# schematic.net
KiCad netlist of a schematic drawn in EasyEDA
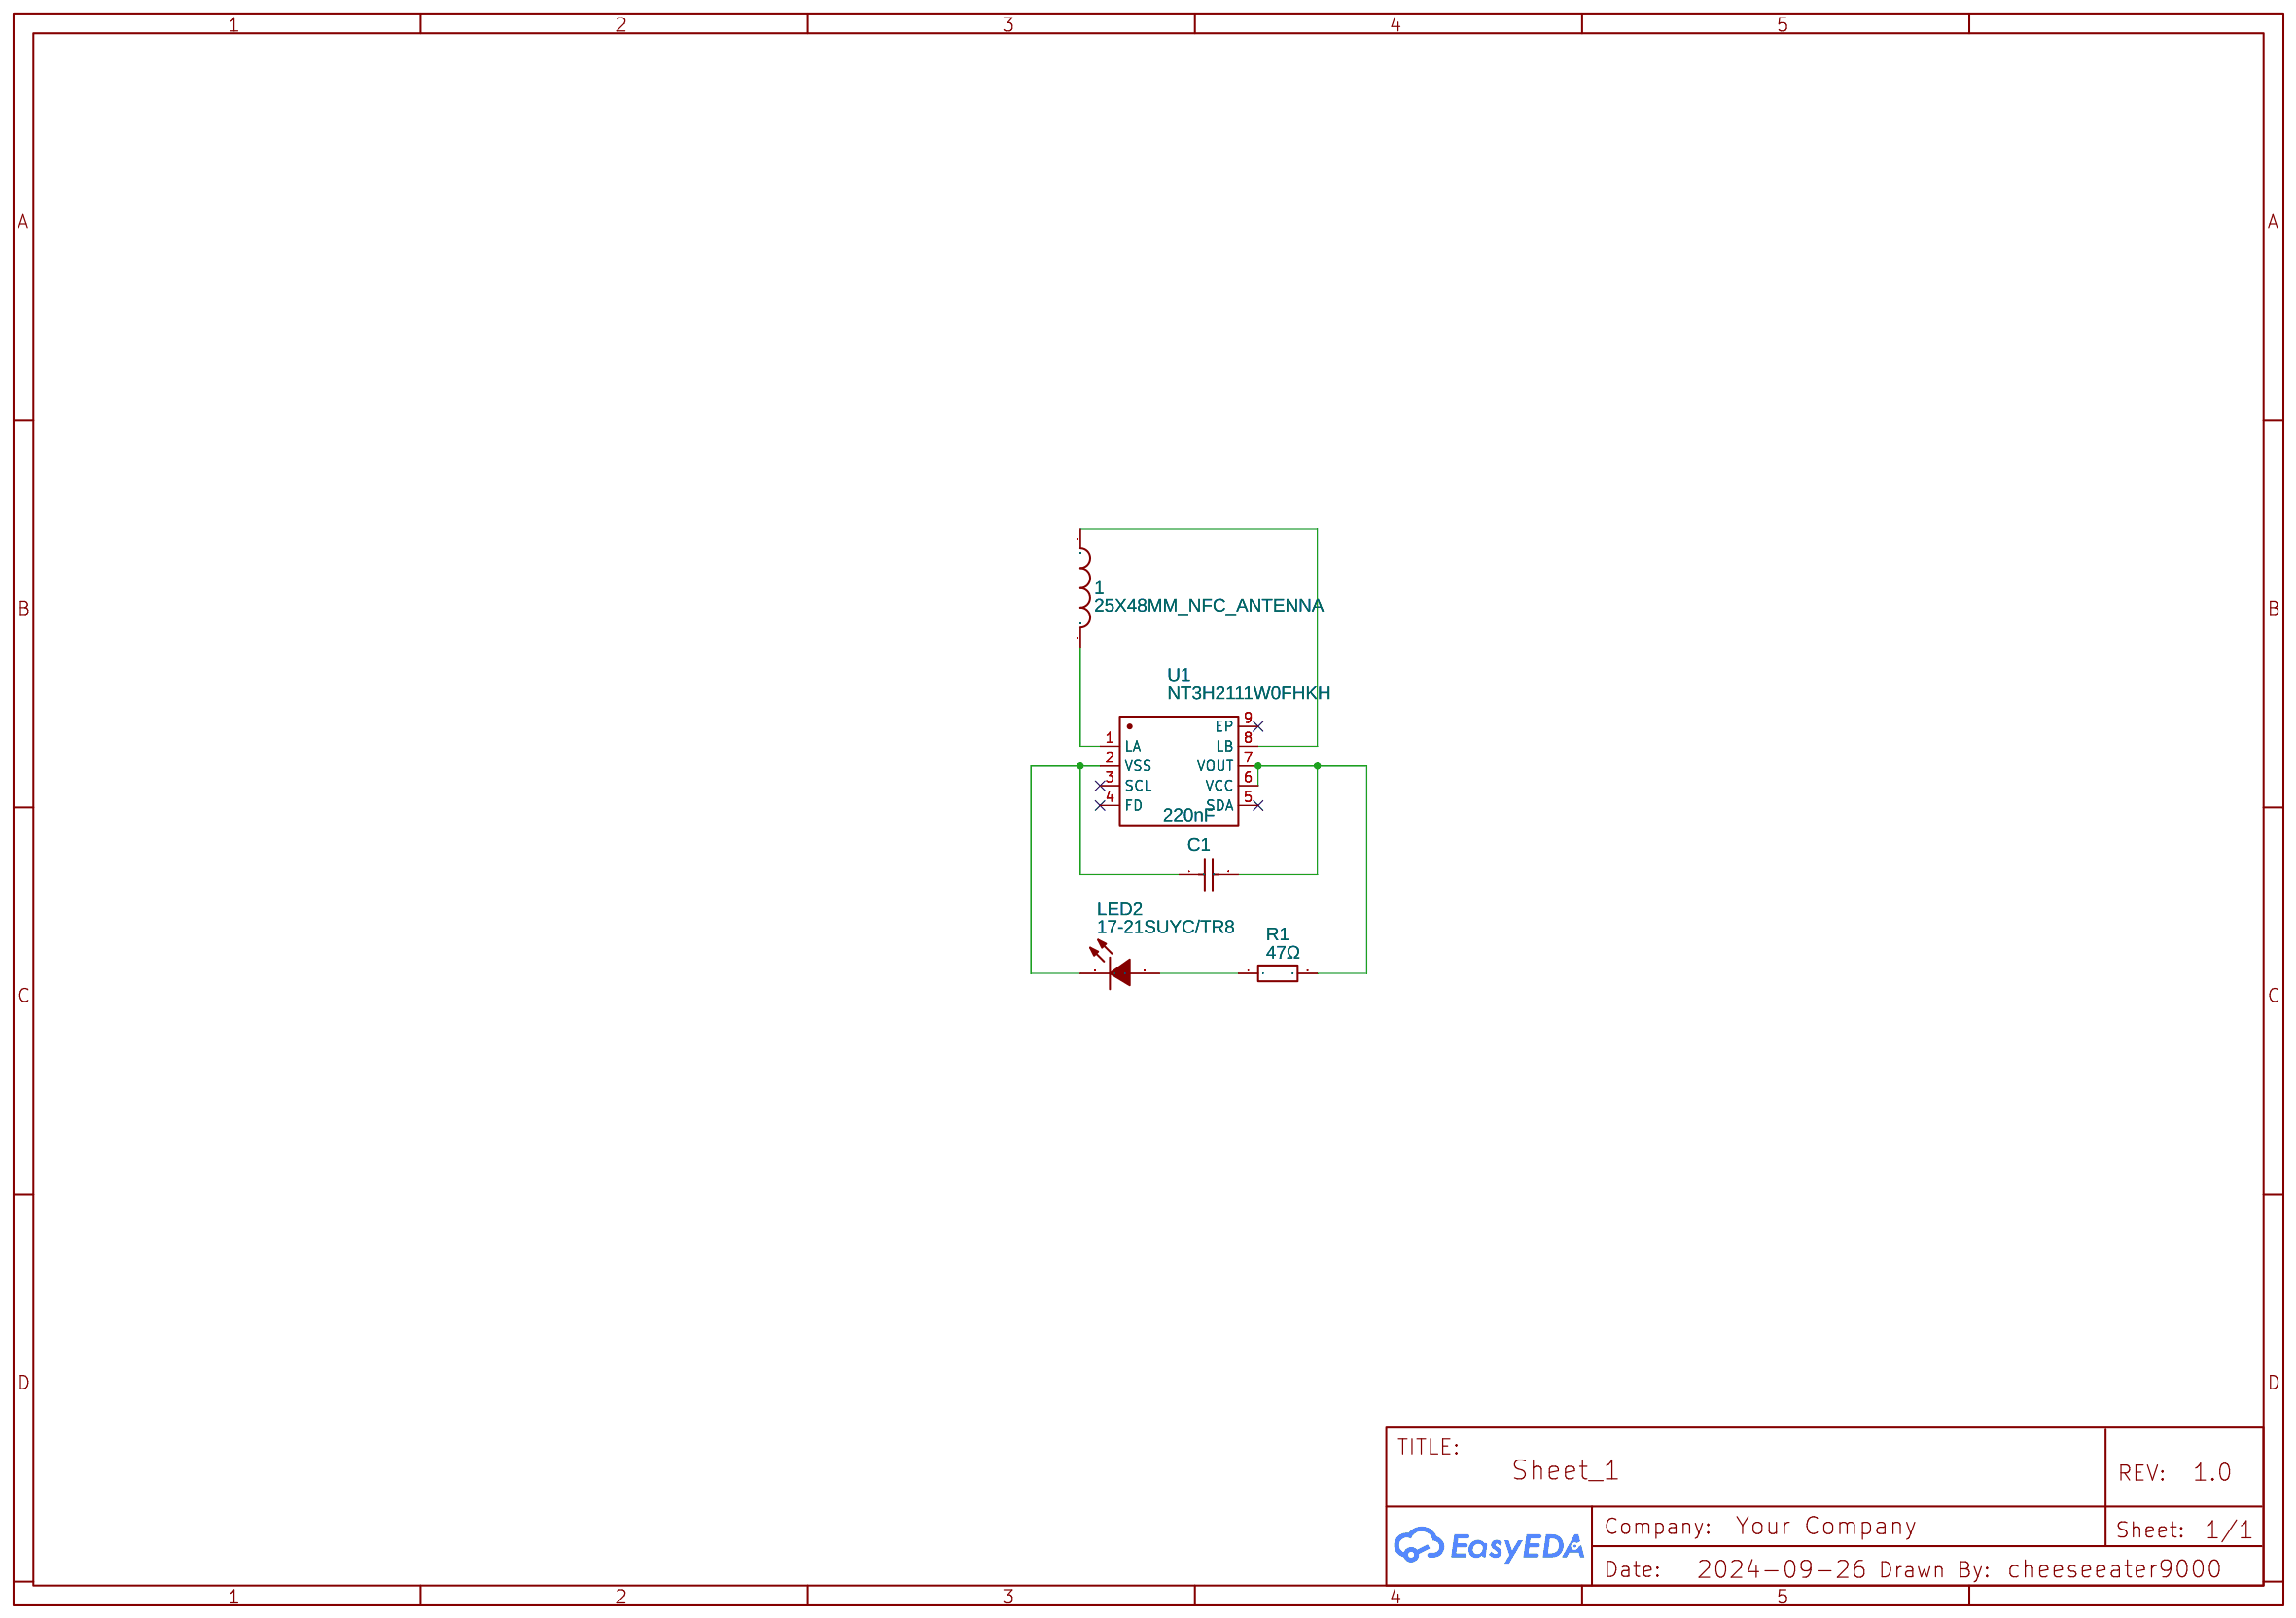
[diagram p0: schematic sheet]

(export (version "E")
  (design (tool "Eeschema 10.0.6"))
  (components
    (comp (ref "1") (value "25X48MM_NFC_ANTENNA") (libsource (lib "") (part "25X48MM_NFC_ANTENNA")))
    (comp (ref "C1")
      (value "220nF")
      (fields
        (field (name "Manufacturer Part") "CL10B224KA8NNNC")
        (field (name "Manufacturer") "SAMSUNG(三星)")
      )
      (libsource (lib "") (part "CL10B224KA8NNNC"))
    )
    (comp (ref "LED2")
      (value "17-21SUYC/TR8")
      (fields (field (name "Manufacturer Part") "KT-0805黄灯") (field (name "Manufacturer") "KENTO"))
      (libsource (lib "") (part "17-21SUYC/TR8"))
    )
    (comp (ref "R1")
      (value "47Ω")
      (fields
        (field (name "Manufacturer Part") "0603WAF470JT5E")
        (field (name "Manufacturer") "UNI-ROYAL(厚声)")
      )
      (libsource (lib "") (part "0603WAF470JT5E"))
    )
    (comp (ref "U1")
      (value "NT3H2111W0FHKH")
      (fields (field (name "Manufacturer") "NXP(恩智浦)"))
      (libsource (lib "") (part "NT3H2111W0FHKH"))
    )
  )
  (nets
    (net (code "1") (name "Net-(LED2-+)") (class "Default")
      (node (ref "LED2") (pin "1") (pinfunction "+_1") (pintype "unspecified"))
      (node (ref "R1") (pin "1") (pinfunction "1_1") (pintype "input"))
    )
    (net (code "2") (name "Net-(LED2--)") (class "Default")
      (node (ref "C1") (pin "1") (pinfunction "1_1") (pintype "input"))
      (node (ref "LED2") (pin "2") (pinfunction "-_2") (pintype "unspecified"))
      (node (ref "U1") (pin "2") (pinfunction "VSS_2") (pintype "unspecified"))
    )
    (net (code "3") (name "Net-(U1-LA)") (class "Default")
      (node (ref "1") (pin "P$2") (pinfunction "P$2_P$2") (pintype "bidirectional"))
      (node (ref "U1") (pin "1") (pinfunction "LA_1") (pintype "unspecified"))
    )
    (net (code "4") (name "Net-(U1-LB)") (class "Default")
      (node (ref "1") (pin "P$1") (pinfunction "P$1_P$1") (pintype "bidirectional"))
      (node (ref "U1") (pin "8") (pinfunction "LB_8") (pintype "unspecified"))
    )
    (net (code "5") (name "Net-(U1-VCC)") (class "Default")
      (node (ref "C1") (pin "2") (pinfunction "2_2") (pintype "input"))
      (node (ref "R1") (pin "2") (pinfunction "2_2") (pintype "input"))
      (node (ref "U1") (pin "6") (pinfunction "VCC_6") (pintype "unspecified"))
      (node (ref "U1") (pin "7") (pinfunction "VOUT_7") (pintype "unspecified"))
    )
    (net (code "6") (name "unconnected-(U1-EP-Pad9)") (class "Default")
      (node (ref "U1") (pin "9") (pinfunction "EP_9") (pintype "unspecified+no_connect"))
    )
    (net (code "7") (name "unconnected-(U1-FD-Pad4)") (class "Default")
      (node (ref "U1") (pin "4") (pinfunction "FD_4") (pintype "unspecified+no_connect"))
    )
    (net (code "8") (name "unconnected-(U1-SCL-Pad3)") (class "Default")
      (node (ref "U1") (pin "3") (pinfunction "SCL_3") (pintype "unspecified+no_connect"))
    )
    (net (code "9") (name "unconnected-(U1-SDA-Pad5)") (class "Default")
      (node (ref "U1") (pin "5") (pinfunction "SDA_5") (pintype "unspecified+no_connect"))
    )
  )
)
